# DCDC_AP62600_5V.net
KiCad netlist of a schematic drawn in Altium Designer
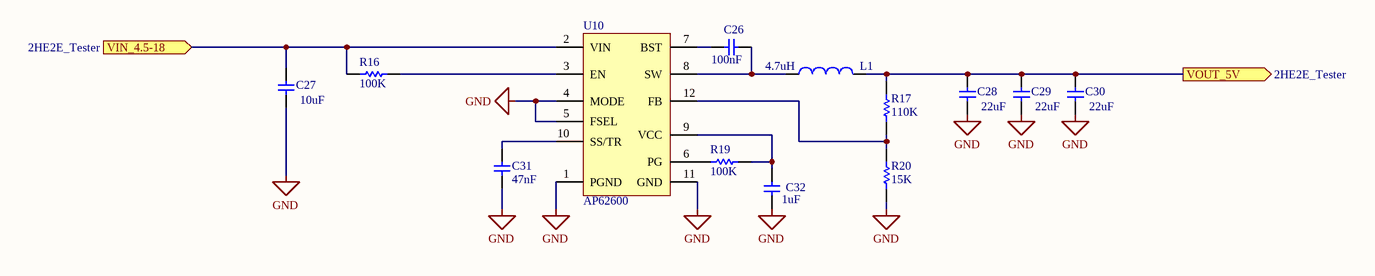
[diagram p0: DCDC_AP62600_5V.SchDoc]

(export (version "E")
  (design (tool "Eeschema 10.0.6"))
  (components
    (comp (ref "C26")
      (value "100nF")
      (footprint "0603M-C")
      (description "Ceramic Capacitor")
      (fields (field (name "Comment") "Cap Ceramic"))
      (libsource (lib "Plume") (part "Cap Ceramic"))
    )
    (comp (ref "C27")
      (value "10uF")
      (footprint "0603M")
      (description "Ceramic Capacitor 16V")
      (fields (field (name "Comment") "Cap Ceramic"))
      (libsource (lib "Plume") (part "Cap Ceramic"))
    )
    (comp (ref "C28")
      (value "22uF")
      (footprint "0603M")
      (description "Ceramic Capacitor 10V")
      (fields (field (name "Comment") "Cap Ceramic"))
      (libsource (lib "Plume") (part "Cap Ceramic"))
    )
    (comp (ref "C29")
      (value "22uF")
      (footprint "0603M")
      (description "Ceramic Capacitor 10V")
      (fields (field (name "Comment") "Cap Ceramic"))
      (libsource (lib "Plume") (part "Cap Ceramic"))
    )
    (comp (ref "C30")
      (value "22uF")
      (footprint "0603M")
      (description "Ceramic Capacitor 10V")
      (fields (field (name "Comment") "Cap Ceramic"))
      (libsource (lib "Plume") (part "Cap Ceramic"))
    )
    (comp (ref "C31")
      (value "47nF")
      (footprint "0603M")
      (description "Ceramic Capacitor 50V")
      (fields (field (name "Comment") "Cap Ceramic"))
      (libsource (lib "Plume") (part "Cap Ceramic"))
    )
    (comp (ref "C32")
      (value "1uF")
      (footprint "0603M-C")
      (description "Ceramic Capacitor 16V")
      (fields (field (name "Comment") "Cap Ceramic"))
      (libsource (lib "Plume") (part "Cap Ceramic"))
    )
    (comp (ref "L1")
      (value "4.7uH")
      (footprint "WE-LQSH_4020")
      (description "74405042047 WE-LQSH SMT High Saturation Power Inductor")
      (fields (field (name "Comment") "Induttanza"))
      (libsource (lib "Plume") (part "Induttanza"))
    )
    (comp (ref "R16")
      (value "100K")
      (footprint "0603M")
      (description "Resistor")
      (libsource (lib "Plume") (part "Resistor"))
    )
    (comp (ref "R17")
      (value "110K")
      (footprint "0603M")
      (description "Resistor")
      (libsource (lib "Plume") (part "Resistor"))
    )
    (comp (ref "R19")
      (value "100K")
      (footprint "0603M")
      (description "Resistor")
      (libsource (lib "Plume") (part "Resistor"))
    )
    (comp (ref "R20")
      (value "15K")
      (footprint "0603M")
      (description "Resistor")
      (libsource (lib "Plume") (part "Resistor"))
    )
    (comp (ref "U10")
      (value "AP62600")
      (footprint "VQFN2030-12(Type A)")
      (description "4.5V TO 18VINPUT, 6A SYNCHRONOUS BUCK CONVERTER")
      (libsource (lib "Plume") (part "AP62600"))
    )
  )
  (nets
    (net (code "1") (name "/VIN_4.5-18") (class "Default")
      (node (ref "C27") (pin "2") (pinfunction "2_2") (pintype "passive"))
      (node (ref "R16") (pin "1") (pinfunction "1_1") (pintype "passive"))
      (node (ref "U10") (pin "2") (pinfunction "VIN_2") (pintype "passive"))
    )
    (net (code "2") (name "/VOUT_5V") (class "Default")
      (node (ref "C28") (pin "2") (pinfunction "2_2") (pintype "passive"))
      (node (ref "C29") (pin "2") (pinfunction "2_2") (pintype "passive"))
      (node (ref "C30") (pin "2") (pinfunction "2_2") (pintype "passive"))
      (node (ref "L1") (pin "2") (pinfunction "2_2") (pintype "passive"))
      (node (ref "R17") (pin "2") (pinfunction "2_2") (pintype "passive"))
    )
    (net (code "3") (name "GND") (class "Default")
      (node (ref "C27") (pin "1") (pinfunction "1_1") (pintype "passive"))
      (node (ref "C28") (pin "1") (pinfunction "1_1") (pintype "passive"))
      (node (ref "C29") (pin "1") (pinfunction "1_1") (pintype "passive"))
      (node (ref "C30") (pin "1") (pinfunction "1_1") (pintype "passive"))
      (node (ref "C31") (pin "1") (pinfunction "1_1") (pintype "passive"))
      (node (ref "C32") (pin "1") (pinfunction "1_1") (pintype "passive"))
      (node (ref "R20") (pin "1") (pinfunction "1_1") (pintype "passive"))
      (node (ref "U10") (pin "1") (pinfunction "PGND_1") (pintype "passive"))
      (node (ref "U10") (pin "11") (pinfunction "GND_11") (pintype "passive"))
      (node (ref "U10") (pin "4") (pinfunction "MODE_4") (pintype "passive"))
      (node (ref "U10") (pin "5") (pinfunction "FSEL_5") (pintype "passive"))
    )
    (net (code "4") (name "Net-(U10-BST)") (class "Default")
      (node (ref "C26") (pin "1") (pinfunction "1_1") (pintype "passive"))
      (node (ref "U10") (pin "7") (pinfunction "BST_7") (pintype "passive"))
    )
    (net (code "5") (name "Net-(U10-EN)") (class "Default")
      (node (ref "R16") (pin "2") (pinfunction "2_2") (pintype "passive"))
      (node (ref "U10") (pin "3") (pinfunction "EN_3") (pintype "passive"))
    )
    (net (code "6") (name "Net-(U10-FB)") (class "Default")
      (node (ref "R17") (pin "1") (pinfunction "1_1") (pintype "passive"))
      (node (ref "R20") (pin "2") (pinfunction "2_2") (pintype "passive"))
      (node (ref "U10") (pin "12") (pinfunction "FB_12") (pintype "passive"))
    )
    (net (code "7") (name "Net-(U10-PG)") (class "Default")
      (node (ref "R19") (pin "1") (pinfunction "1_1") (pintype "passive"))
      (node (ref "U10") (pin "6") (pinfunction "PG_6") (pintype "passive"))
    )
    (net (code "8") (name "Net-(U10-SS{slash}TR)") (class "Default")
      (node (ref "C31") (pin "2") (pinfunction "2_2") (pintype "passive"))
      (node (ref "U10") (pin "10") (pinfunction "SS/TR_10") (pintype "passive"))
    )
    (net (code "9") (name "Net-(U10-SW)") (class "Default")
      (node (ref "C26") (pin "2") (pinfunction "2_2") (pintype "passive"))
      (node (ref "L1") (pin "1") (pinfunction "1_1") (pintype "passive"))
      (node (ref "U10") (pin "8") (pinfunction "SW_8") (pintype "passive"))
    )
    (net (code "10") (name "Net-(U10-VCC)") (class "Default")
      (node (ref "C32") (pin "2") (pinfunction "2_2") (pintype "passive"))
      (node (ref "R19") (pin "2") (pinfunction "2_2") (pintype "passive"))
      (node (ref "U10") (pin "9") (pinfunction "VCC_9") (pintype "passive"))
    )
  )
)
